# domovoy-ff1.net
KiCad netlist of a schematic drawn in EAGLE
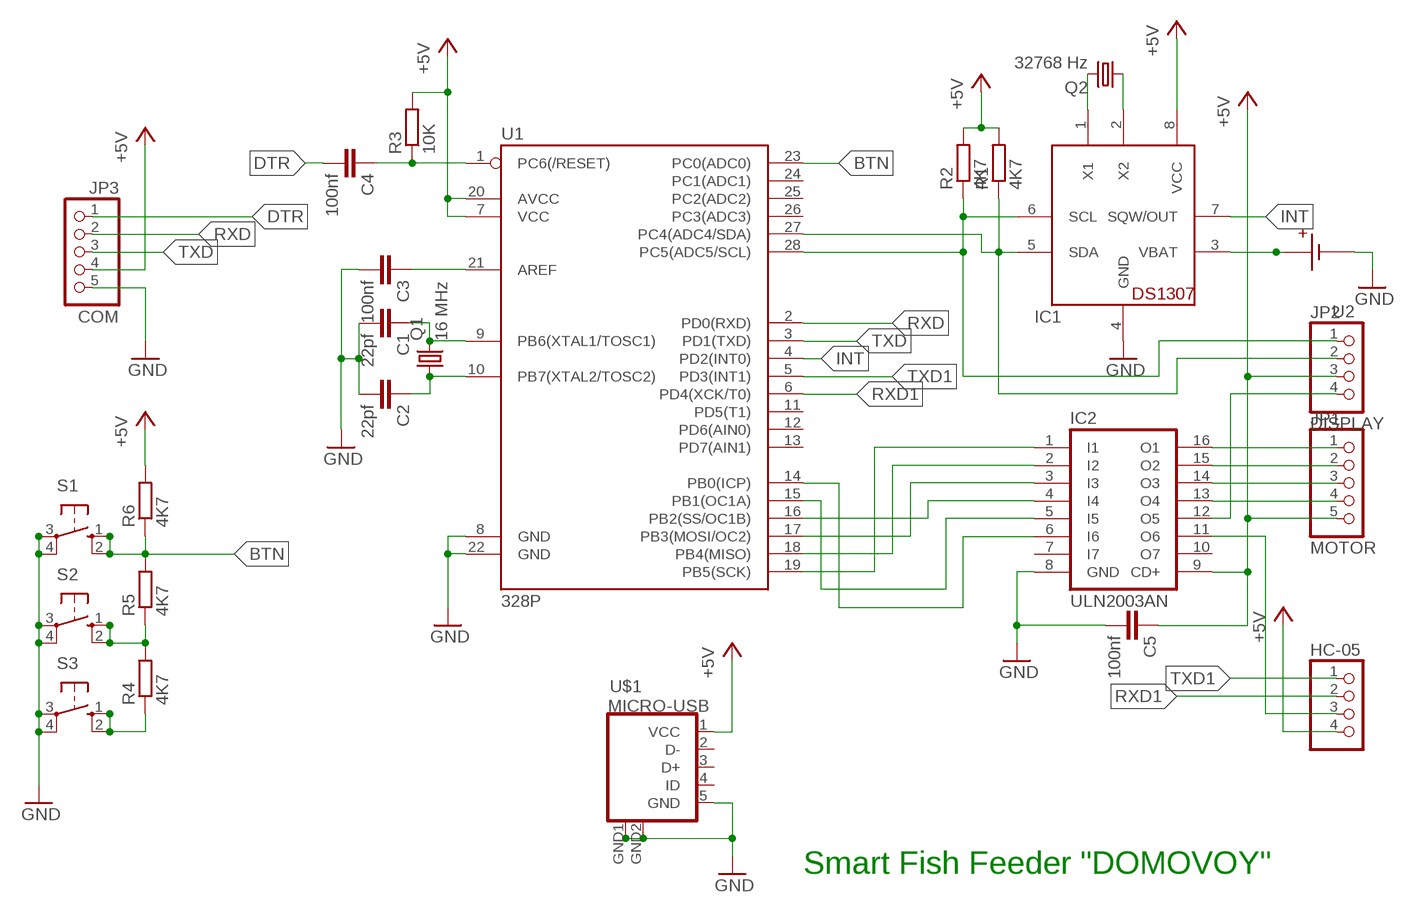
[diagram p0: schematic, sheet 1]

(export (version "E")
  (design (tool "Eeschema 10.0.6"))
  (components
    (comp (ref "C1")
      (value "22pf")
      (footprint "eagle-import:C1206")
      (libsource (lib "eagle-import") (part "C-EUC1206"))
    )
    (comp (ref "C2")
      (value "22pf")
      (footprint "eagle-import:C1206")
      (libsource (lib "eagle-import") (part "C-EUC1206"))
    )
    (comp (ref "C3")
      (value "100nf")
      (footprint "eagle-import:C1206")
      (libsource (lib "eagle-import") (part "C-EUC1206"))
    )
    (comp (ref "C4")
      (value "100nf")
      (footprint "eagle-import:C1206")
      (libsource (lib "eagle-import") (part "C-EUC1206"))
    )
    (comp (ref "C5")
      (value "100nf")
      (footprint "eagle-import:C1206")
      (libsource (lib "eagle-import") (part "C-EUC1206"))
    )
    (comp (ref "HC-05")
      (value "PINHD-1X4")
      (footprint "eagle-import:1X04")
      (libsource (lib "eagle-import") (part "PINHD-1X4"))
    )
    (comp (ref "IC1")
      (value "DS1307")
      (footprint "eagle-import:DIL08")
      (libsource (lib "eagle-import") (part "DS1307"))
    )
    (comp (ref "IC2")
      (value "ULN2003AN")
      (footprint "eagle-import:DIL16")
      (libsource (lib "eagle-import") (part "ULN2003AN"))
    )
    (comp (ref "JP1")
      (value "MOTOR")
      (footprint "eagle-import:1X05")
      (libsource (lib "eagle-import") (part "PINHD-1X5"))
    )
    (comp (ref "JP2")
      (value "DISPLAY")
      (footprint "eagle-import:1X04")
      (libsource (lib "eagle-import") (part "PINHD-1X4"))
    )
    (comp (ref "JP3")
      (value "COM")
      (footprint "eagle-import:1X05")
      (libsource (lib "eagle-import") (part "PINHD-1X5"))
    )
    (comp (ref "Q1")
      (value "16 MHz")
      (footprint "eagle-import:HC49_S")
      (libsource (lib "eagle-import") (part "CRYSTALHC49S"))
    )
    (comp (ref "Q2")
      (value "32768 Hz")
      (footprint "eagle-import:TC38H")
      (libsource (lib "eagle-import") (part "CRYSTALTC38H"))
    )
    (comp (ref "R1")
      (value "4K7")
      (footprint "eagle-import:R1206")
      (libsource (lib "eagle-import") (part "R-EU_R1206"))
    )
    (comp (ref "R2")
      (value "4K7")
      (footprint "eagle-import:R1206")
      (libsource (lib "eagle-import") (part "R-EU_R1206"))
    )
    (comp (ref "R3")
      (value "10K")
      (footprint "eagle-import:R1206")
      (libsource (lib "eagle-import") (part "R-EU_R1206"))
    )
    (comp (ref "R4")
      (value "4K7")
      (footprint "eagle-import:R1206")
      (libsource (lib "eagle-import") (part "R-EU_R1206"))
    )
    (comp (ref "R5")
      (value "4K7")
      (footprint "eagle-import:R1206")
      (libsource (lib "eagle-import") (part "R-EU_R1206"))
    )
    (comp (ref "R6")
      (value "4K7")
      (footprint "eagle-import:R1206")
      (libsource (lib "eagle-import") (part "R-EU_R1206"))
    )
    (comp (ref "S1")
      (value "10-XX")
      (footprint "eagle-import:B3F-10XX")
      (fields (field (name "MPN") "B3F-1000"))
      (libsource (lib "eagle-import") (part "10-XX"))
    )
    (comp (ref "S2")
      (value "10-XX")
      (footprint "eagle-import:B3F-10XX")
      (fields (field (name "MPN") "B3F-1000"))
      (libsource (lib "eagle-import") (part "10-XX"))
    )
    (comp (ref "S3")
      (value "10-XX")
      (footprint "eagle-import:B3F-10XX")
      (fields (field (name "MPN") "B3F-1000"))
      (libsource (lib "eagle-import") (part "10-XX"))
    )
    (comp (ref "U$1")
      (value "MICRO-USB")
      (footprint "eagle-import:MICRO-USB")
      (libsource (lib "eagle-import") (part "MICRO-USB"))
    )
    (comp (ref "U1")
      (value "328P")
      (footprint "eagle-import:DIP28")
      (libsource (lib "eagle-import") (part "ATMEGA328P_PDIP"))
    )
    (comp (ref "U2")
      (value "CR2032-HOLDERSTANDARD")
      (footprint "eagle-import:DIP")
      (libsource (lib "eagle-import") (part "CR2032-HOLDERSTANDARD"))
    )
  )
  (nets
    (net (code "1") (name "+5V") (class "Default")
      (node (ref "C5") (pin "1") (pinfunction "1_1") (pintype "passive"))
      (node (ref "HC-05") (pin "4") (pinfunction "4_4") (pintype "passive"))
      (node (ref "IC1") (pin "8") (pinfunction "VCC_8") (pintype "power_in"))
      (node (ref "IC2") (pin "9") (pinfunction "CD+_9") (pintype "passive"))
      (node (ref "JP1") (pin "5") (pinfunction "5_5") (pintype "passive"))
      (node (ref "JP2") (pin "3") (pinfunction "3_3") (pintype "passive"))
      (node (ref "JP3") (pin "4") (pinfunction "4_4") (pintype "passive"))
      (node (ref "R1") (pin "2") (pinfunction "2_2") (pintype "passive"))
      (node (ref "R2") (pin "2") (pinfunction "2_2") (pintype "passive"))
      (node (ref "R3") (pin "2") (pinfunction "2_2") (pintype "passive"))
      (node (ref "R6") (pin "2") (pinfunction "2_2") (pintype "passive"))
      (node (ref "U$1") (pin "1") (pinfunction "VCC_1") (pintype "power_in"))
      (node (ref "U1") (pin "20") (pinfunction "AVCC_20") (pintype "bidirectional"))
      (node (ref "U1") (pin "7") (pinfunction "VCC_7") (pintype "bidirectional"))
    )
    (net (code "2") (name "BTN") (class "Default")
      (node (ref "R5") (pin "2") (pinfunction "2_2") (pintype "passive"))
      (node (ref "R6") (pin "1") (pinfunction "1_1") (pintype "passive"))
      (node (ref "S1") (pin "1") (pinfunction "S_1") (pintype "passive"))
      (node (ref "S1") (pin "2") (pinfunction "S1_2") (pintype "passive"))
      (node (ref "U1") (pin "23") (pinfunction "PC0(ADC0)_23") (pintype "bidirectional"))
    )
    (net (code "3") (name "DTR") (class "Default")
      (node (ref "C4") (pin "2") (pinfunction "2_2") (pintype "passive"))
      (node (ref "JP3") (pin "1") (pinfunction "1_1") (pintype "passive"))
    )
    (net (code "4") (name "GND") (class "Default")
      (node (ref "C1") (pin "2") (pinfunction "2_2") (pintype "passive"))
      (node (ref "C2") (pin "2") (pinfunction "2_2") (pintype "passive"))
      (node (ref "C3") (pin "2") (pinfunction "2_2") (pintype "passive"))
      (node (ref "C5") (pin "2") (pinfunction "2_2") (pintype "passive"))
      (node (ref "IC1") (pin "4") (pinfunction "GND_4") (pintype "power_in"))
      (node (ref "IC2") (pin "8") (pinfunction "GND_8") (pintype "power_in"))
      (node (ref "JP3") (pin "5") (pinfunction "5_5") (pintype "passive"))
      (node (ref "S1") (pin "3") (pinfunction "P_3") (pintype "passive"))
      (node (ref "S1") (pin "4") (pinfunction "P1_4") (pintype "passive"))
      (node (ref "S2") (pin "3") (pinfunction "P_3") (pintype "passive"))
      (node (ref "S2") (pin "4") (pinfunction "P1_4") (pintype "passive"))
      (node (ref "S3") (pin "3") (pinfunction "P_3") (pintype "passive"))
      (node (ref "S3") (pin "4") (pinfunction "P1_4") (pintype "passive"))
      (node (ref "U$1") (pin "5") (pinfunction "GND_5") (pintype "power_in"))
      (node (ref "U$1") (pin "GND1") (pinfunction "GND_GND1") (pintype "power_in"))
      (node (ref "U$1") (pin "GND2") (pinfunction "GND_GND2") (pintype "power_in"))
      (node (ref "U1") (pin "22") (pinfunction "GND_22") (pintype "bidirectional"))
      (node (ref "U1") (pin "8") (pinfunction "GND_8") (pintype "bidirectional"))
      (node (ref "U2") (pin "GND") (pinfunction "GND_GND") (pintype "bidirectional"))
    )
    (net (code "5") (name "INT") (class "Default")
      (node (ref "IC1") (pin "7") (pinfunction "SQW/OUT_7") (pintype "bidirectional"))
      (node (ref "U1") (pin "4") (pinfunction "PD2(INT0)_4") (pintype "bidirectional"))
    )
    (net (code "6") (name "Net-(IC1-SCL)") (class "Default")
      (node (ref "IC1") (pin "6") (pinfunction "SCL_6") (pintype "bidirectional"))
      (node (ref "JP2") (pin "1") (pinfunction "1_1") (pintype "passive"))
      (node (ref "R2") (pin "1") (pinfunction "1_1") (pintype "passive"))
      (node (ref "U1") (pin "28") (pinfunction "PC5(ADC5/SCL)_28") (pintype "bidirectional"))
    )
    (net (code "7") (name "Net-(IC1-SDA)") (class "Default")
      (node (ref "IC1") (pin "5") (pinfunction "SDA_5") (pintype "bidirectional"))
      (node (ref "JP2") (pin "2") (pinfunction "2_2") (pintype "passive"))
      (node (ref "R1") (pin "1") (pinfunction "1_1") (pintype "passive"))
      (node (ref "U1") (pin "27") (pinfunction "PC4(ADC4/SDA)_27") (pintype "bidirectional"))
    )
    (net (code "8") (name "Net-(IC1-VBAT)") (class "Default")
      (node (ref "IC1") (pin "3") (pinfunction "VBAT_3") (pintype "power_in"))
      (node (ref "U2") (pin "POWER") (pinfunction "POWER_POWER") (pintype "bidirectional"))
    )
    (net (code "9") (name "Net-(IC1-X1)") (class "Default")
      (node (ref "IC1") (pin "1") (pinfunction "X1_1") (pintype "passive"))
      (node (ref "Q2") (pin "2") (pinfunction "2_2") (pintype "passive"))
    )
    (net (code "10") (name "Net-(IC1-X2)") (class "Default")
      (node (ref "IC1") (pin "2") (pinfunction "X2_2") (pintype "passive"))
      (node (ref "Q2") (pin "1") (pinfunction "1_1") (pintype "passive"))
    )
    (net (code "11") (name "Net-(IC2-I1)") (class "Default")
      (node (ref "IC2") (pin "1") (pinfunction "I1_1") (pintype "input"))
      (node (ref "U1") (pin "19") (pinfunction "PB5(SCK)_19") (pintype "bidirectional"))
    )
    (net (code "12") (name "Net-(IC2-I2)") (class "Default")
      (node (ref "IC2") (pin "2") (pinfunction "I2_2") (pintype "input"))
      (node (ref "U1") (pin "18") (pinfunction "PB4(MISO)_18") (pintype "bidirectional"))
    )
    (net (code "13") (name "Net-(IC2-I3)") (class "Default")
      (node (ref "IC2") (pin "3") (pinfunction "I3_3") (pintype "input"))
      (node (ref "U1") (pin "17") (pinfunction "PB3(MOSI/OC2)_17") (pintype "bidirectional"))
    )
    (net (code "14") (name "Net-(IC2-I4)") (class "Default")
      (node (ref "IC2") (pin "4") (pinfunction "I4_4") (pintype "input"))
      (node (ref "U1") (pin "16") (pinfunction "PB2(SS/OC1B)_16") (pintype "bidirectional"))
    )
    (net (code "15") (name "Net-(IC2-I5)") (class "Default")
      (node (ref "IC2") (pin "5") (pinfunction "I5_5") (pintype "input"))
      (node (ref "U1") (pin "15") (pinfunction "PB1(OC1A)_15") (pintype "bidirectional"))
    )
    (net (code "16") (name "Net-(IC2-I6)") (class "Default")
      (node (ref "IC2") (pin "6") (pinfunction "I6_6") (pintype "input"))
      (node (ref "U1") (pin "14") (pinfunction "PB0(ICP)_14") (pintype "bidirectional"))
    )
    (net (code "17") (name "Net-(IC2-O1)") (class "Default")
      (node (ref "IC2") (pin "16") (pinfunction "O1_16") (pintype "open_collector"))
      (node (ref "JP1") (pin "1") (pinfunction "1_1") (pintype "passive"))
    )
    (net (code "18") (name "Net-(IC2-O2)") (class "Default")
      (node (ref "IC2") (pin "15") (pinfunction "O2_15") (pintype "open_collector"))
      (node (ref "JP1") (pin "2") (pinfunction "2_2") (pintype "passive"))
    )
    (net (code "19") (name "Net-(IC2-O3)") (class "Default")
      (node (ref "IC2") (pin "14") (pinfunction "O3_14") (pintype "open_collector"))
      (node (ref "JP1") (pin "3") (pinfunction "3_3") (pintype "passive"))
    )
    (net (code "20") (name "Net-(IC2-O4)") (class "Default")
      (node (ref "IC2") (pin "13") (pinfunction "O4_13") (pintype "open_collector"))
      (node (ref "JP1") (pin "4") (pinfunction "4_4") (pintype "passive"))
    )
    (net (code "21") (name "Net-(IC2-O5)") (class "Default")
      (node (ref "IC2") (pin "12") (pinfunction "O5_12") (pintype "open_collector"))
      (node (ref "JP2") (pin "4") (pinfunction "4_4") (pintype "passive"))
    )
    (net (code "22") (name "Net-(IC2-O6)") (class "Default")
      (node (ref "HC-05") (pin "3") (pinfunction "3_3") (pintype "passive"))
      (node (ref "IC2") (pin "11") (pinfunction "O6_11") (pintype "open_collector"))
    )
    (net (code "23") (name "Net-(S2-S)") (class "Default")
      (node (ref "R4") (pin "2") (pinfunction "2_2") (pintype "passive"))
      (node (ref "R5") (pin "1") (pinfunction "1_1") (pintype "passive"))
      (node (ref "S2") (pin "1") (pinfunction "S_1") (pintype "passive"))
      (node (ref "S2") (pin "2") (pinfunction "S1_2") (pintype "passive"))
    )
    (net (code "24") (name "Net-(S3-S)") (class "Default")
      (node (ref "R4") (pin "1") (pinfunction "1_1") (pintype "passive"))
      (node (ref "S3") (pin "1") (pinfunction "S_1") (pintype "passive"))
      (node (ref "S3") (pin "2") (pinfunction "S1_2") (pintype "passive"))
    )
    (net (code "25") (name "Net-(U1-AREF)") (class "Default")
      (node (ref "C3") (pin "1") (pinfunction "1_1") (pintype "passive"))
      (node (ref "U1") (pin "21") (pinfunction "AREF_21") (pintype "bidirectional"))
    )
    (net (code "26") (name "Net-(U1-PB6(XTAL1{slash}TOSC1))") (class "Default")
      (node (ref "C1") (pin "1") (pinfunction "1_1") (pintype "passive"))
      (node (ref "Q1") (pin "2") (pinfunction "2_2") (pintype "passive"))
      (node (ref "U1") (pin "9") (pinfunction "PB6(XTAL1/TOSC1)_9") (pintype "bidirectional"))
    )
    (net (code "27") (name "Net-(U1-PB7(XTAL2{slash}TOSC2))") (class "Default")
      (node (ref "C2") (pin "1") (pinfunction "1_1") (pintype "passive"))
      (node (ref "Q1") (pin "1") (pinfunction "1_1") (pintype "passive"))
      (node (ref "U1") (pin "10") (pinfunction "PB7(XTAL2/TOSC2)_10") (pintype "bidirectional"))
    )
    (net (code "28") (name "Net-(U1-PC6({slash}RESET))") (class "Default")
      (node (ref "C4") (pin "1") (pinfunction "1_1") (pintype "passive"))
      (node (ref "R3") (pin "1") (pinfunction "1_1") (pintype "passive"))
      (node (ref "U1") (pin "1") (pinfunction "PC6(/RESET)_1") (pintype "bidirectional"))
    )
    (net (code "29") (name "RXD") (class "Default")
      (node (ref "JP3") (pin "2") (pinfunction "2_2") (pintype "passive"))
      (node (ref "U1") (pin "2") (pinfunction "PD0(RXD)_2") (pintype "bidirectional"))
    )
    (net (code "30") (name "RXD1") (class "Default")
      (node (ref "HC-05") (pin "2") (pinfunction "2_2") (pintype "passive"))
      (node (ref "U1") (pin "6") (pinfunction "PD4(XCK/T0)_6") (pintype "bidirectional"))
    )
    (net (code "31") (name "TXD") (class "Default")
      (node (ref "JP3") (pin "3") (pinfunction "3_3") (pintype "passive"))
      (node (ref "U1") (pin "3") (pinfunction "PD1(TXD)_3") (pintype "bidirectional"))
    )
    (net (code "32") (name "TXD1") (class "Default")
      (node (ref "HC-05") (pin "1") (pinfunction "1_1") (pintype "passive"))
      (node (ref "U1") (pin "5") (pinfunction "PD3(INT1)_5") (pintype "bidirectional"))
    )
    (net (code "33") (name "unconnected-(IC2-I7-Pad7)") (class "Default")
      (node (ref "IC2") (pin "7") (pinfunction "I7_7") (pintype "input"))
    )
    (net (code "34") (name "unconnected-(IC2-O7-Pad10)") (class "Default")
      (node (ref "IC2") (pin "10") (pinfunction "O7_10") (pintype "open_collector"))
    )
    (net (code "35") (name "unconnected-(U$1-D+-Pad3)") (class "Default")
      (node (ref "U$1") (pin "3") (pinfunction "D+_3") (pintype "bidirectional"))
    )
    (net (code "36") (name "unconnected-(U$1-D--Pad2)") (class "Default")
      (node (ref "U$1") (pin "2") (pinfunction "D-_2") (pintype "bidirectional"))
    )
    (net (code "37") (name "unconnected-(U$1-ID-Pad4)") (class "Default")
      (node (ref "U$1") (pin "4") (pinfunction "ID_4") (pintype "bidirectional"))
    )
    (net (code "38") (name "unconnected-(U1-PC1(ADC1)-Pad24)") (class "Default")
      (node (ref "U1") (pin "24") (pinfunction "PC1(ADC1)_24") (pintype "bidirectional"))
    )
    (net (code "39") (name "unconnected-(U1-PC2(ADC2)-Pad25)") (class "Default")
      (node (ref "U1") (pin "25") (pinfunction "PC2(ADC2)_25") (pintype "bidirectional"))
    )
    (net (code "40") (name "unconnected-(U1-PC3(ADC3)-Pad26)") (class "Default")
      (node (ref "U1") (pin "26") (pinfunction "PC3(ADC3)_26") (pintype "bidirectional"))
    )
    (net (code "41") (name "unconnected-(U1-PD5(T1)-Pad11)") (class "Default")
      (node (ref "U1") (pin "11") (pinfunction "PD5(T1)_11") (pintype "bidirectional"))
    )
    (net (code "42") (name "unconnected-(U1-PD6(AIN0)-Pad12)") (class "Default")
      (node (ref "U1") (pin "12") (pinfunction "PD6(AIN0)_12") (pintype "bidirectional"))
    )
    (net (code "43") (name "unconnected-(U1-PD7(AIN1)-Pad13)") (class "Default")
      (node (ref "U1") (pin "13") (pinfunction "PD7(AIN1)_13") (pintype "bidirectional"))
    )
  )
)
